# v1_0.net
KiCad netlist of a schematic drawn in Altium Designer
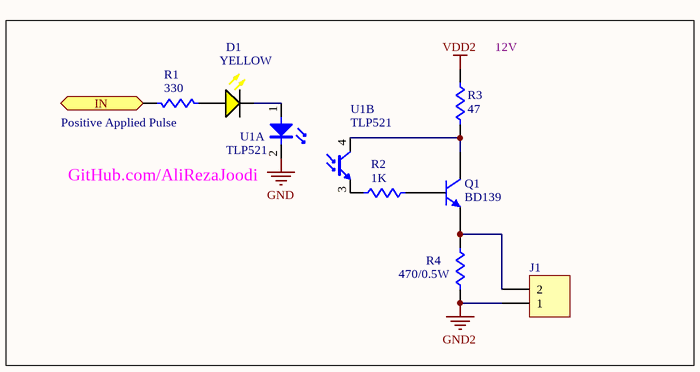
[diagram p0: v1.0.SchDoc]

(export (version "E")
  (design (tool "Eeschema 10.0.6"))
  (components
    (comp (ref "D1")
      (value "YELLOW")
      (footprint "LED_THD_3MM_YELLOW_R")
      (description "LED, Yellow")
      (fields (field (name "MANUFACTURER") "Generic Components") (field (name "PUBLISHER") "Altium Limited"))
      (libsource (lib "Display") (part "LED_YELLOW"))
    )
    (comp (ref "J1")
      (value "2Pin")
      (footprint "Fonics_2PIN_1")
      (description "Header, 2-Pin")
      (fields (field (name "PUBLISHER") "Altium Limited"))
      (libsource (lib "Miscellaneous Connectors") (part "Header 2"))
    )
    (comp (ref "Q1")
      (value "BD139")
      (footprint "TO-226-AA")
      (description "NPN Bipolar Transistor")
      (fields (field (name "PUBLISHER") "Altium Limited"))
      (libsource (lib "Miscellaneous Devices") (part "NPN"))
    )
    (comp (ref "R1")
      (value "330")
      (footprint "0805")
      (description "Resistor")
      (fields (field (name "MANUFACTURER") "Generic Components") (field (name "PUBLISHER") "Altium Limited"))
      (libsource (lib "Miscellaneous Devices") (part "Res1"))
    )
    (comp (ref "R2")
      (value "1K")
      (footprint "RESC3216N")
      (description "Resistor")
      (fields (field (name "MANUFACTURER") "Generic Components") (field (name "PUBLISHER") "Altium Limited"))
      (libsource (lib "Miscellaneous Devices") (part "Res1"))
    )
    (comp (ref "R3")
      (value "47")
      (footprint "RESC3216N")
      (description "Resistor")
      (fields (field (name "MANUFACTURER") "Generic Components") (field (name "PUBLISHER") "Altium Limited"))
      (libsource (lib "Miscellaneous Devices") (part "Res1"))
    )
    (comp (ref "R4")
      (value "470/0.5W")
      (footprint "RESC3216N")
      (description "Resistor")
      (fields (field (name "MANUFACTURER") "Generic Components") (field (name "PUBLISHER") "Altium Limited"))
      (libsource (lib "Miscellaneous Devices") (part "Res1"))
    )
    (comp (ref "U1")
      (value "TLP521")
      (footprint "SMD_4PIN")
      (fields (field (name "PUBLISHER") "Altium Limited"))
      (libsource (lib "my Libraries") (part "Optoisolator"))
    )
  )
  (nets
    (net (code "1") (name "/IN") (class "Default")
      (node (ref "R1") (pin "1") (pinfunction "1_1") (pintype "passive"))
    )
    (net (code "2") (name "GND") (class "Default")
      (node (ref "U1") (pin "2") (pinfunction "K_2") (pintype "power_in"))
    )
    (net (code "3") (name "GND2") (class "Default")
      (node (ref "J1") (pin "1") (pinfunction "1_1") (pintype "passive"))
      (node (ref "R4") (pin "2") (pinfunction "2_2") (pintype "passive"))
    )
    (net (code "4") (name "Net-(D1-A)") (class "Default")
      (node (ref "D1") (pin "1") (pinfunction "A_1") (pintype "passive"))
      (node (ref "R1") (pin "2") (pinfunction "2_2") (pintype "passive"))
    )
    (net (code "5") (name "Net-(D1-K)") (class "Default")
      (node (ref "D1") (pin "2") (pinfunction "K_2") (pintype "passive"))
      (node (ref "U1") (pin "1") (pinfunction "A_1") (pintype "power_in"))
    )
    (net (code "6") (name "Net-(Q1-B)") (class "Default")
      (node (ref "Q1") (pin "2") (pinfunction "B_2") (pintype "passive"))
      (node (ref "R2") (pin "2") (pinfunction "2_2") (pintype "passive"))
    )
    (net (code "7") (name "Net-(Q1-C)") (class "Default")
      (node (ref "Q1") (pin "1") (pinfunction "C_1") (pintype "passive"))
      (node (ref "R3") (pin "2") (pinfunction "2_2") (pintype "passive"))
      (node (ref "U1") (pin "4") (pinfunction "C_4") (pintype "passive"))
    )
    (net (code "8") (name "Net-(Q1-E)") (class "Default")
      (node (ref "J1") (pin "2") (pinfunction "2_2") (pintype "passive"))
      (node (ref "Q1") (pin "3") (pinfunction "E_3") (pintype "passive"))
      (node (ref "R4") (pin "1") (pinfunction "1_1") (pintype "passive"))
    )
    (net (code "9") (name "Net-(U1B-E)") (class "Default")
      (node (ref "R2") (pin "1") (pinfunction "1_1") (pintype "passive"))
      (node (ref "U1") (pin "3") (pinfunction "E_3") (pintype "passive"))
    )
    (net (code "10") (name "VDD2") (class "Default")
      (node (ref "R3") (pin "1") (pinfunction "1_1") (pintype "passive"))
    )
  )
)
